# Smart_Light_Panel4.net
KiCad netlist of a schematic drawn in EAGLE
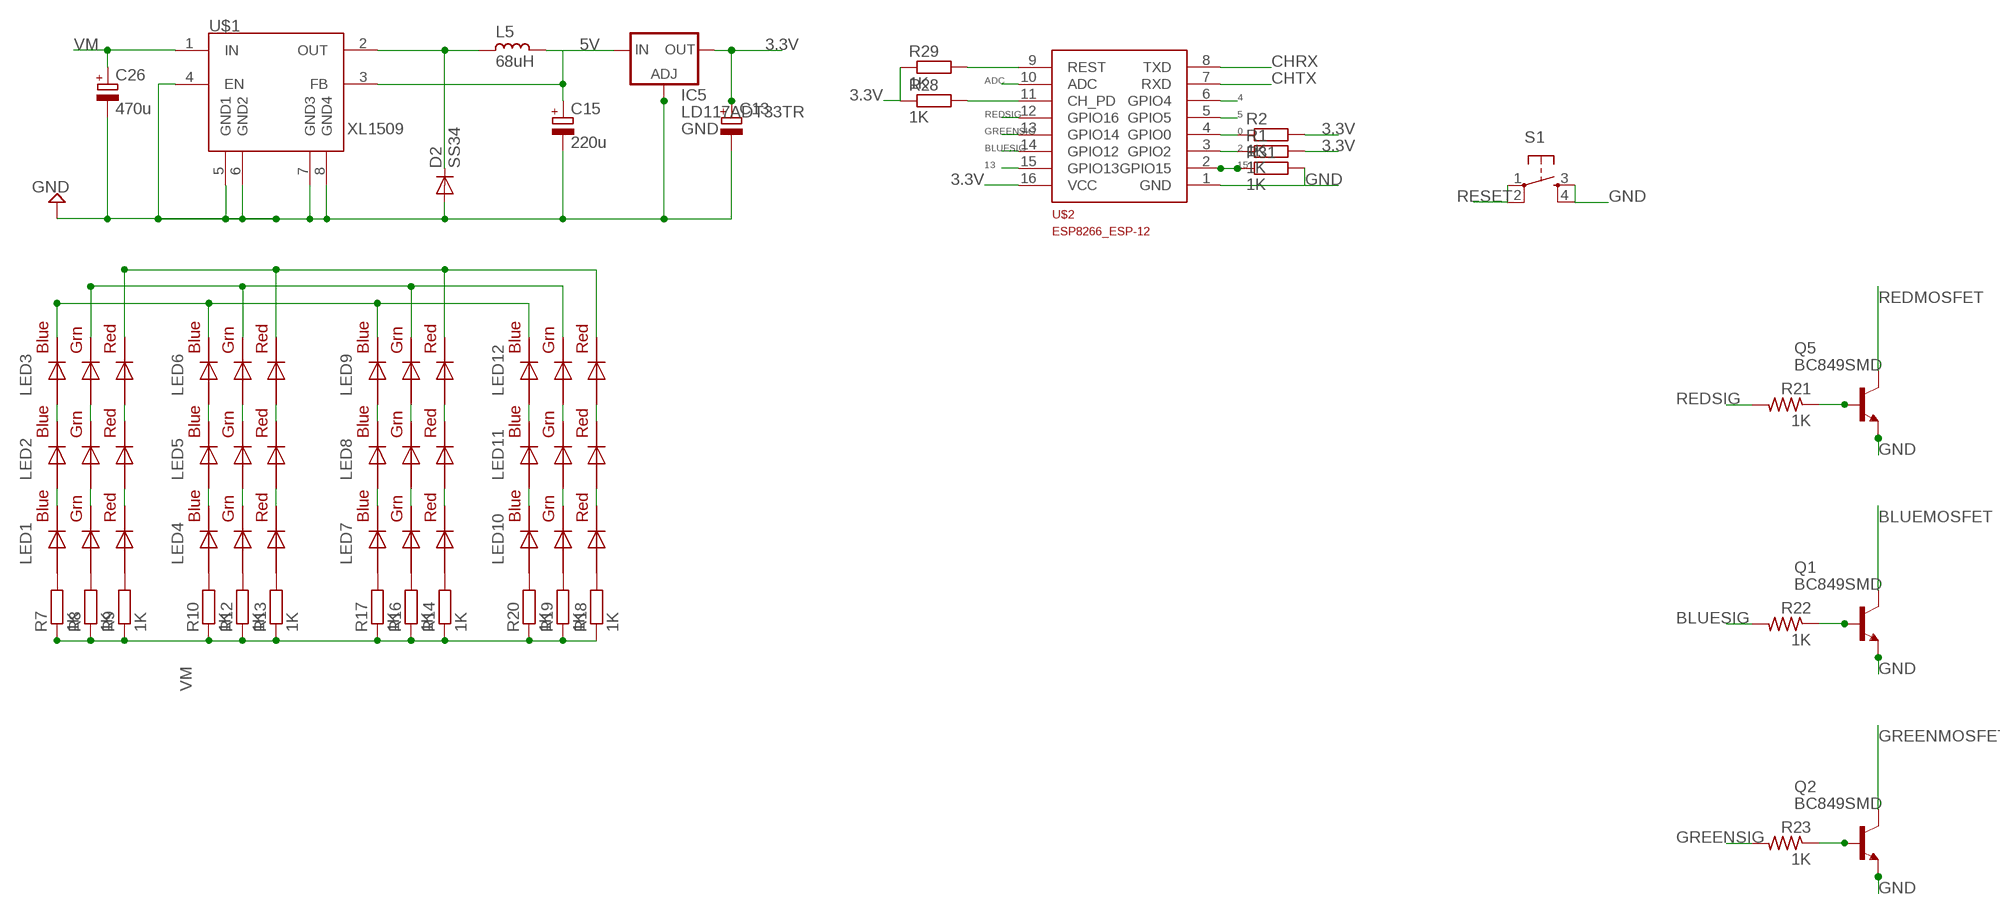
[diagram p0: schematic, sheet 1]

(export (version "E")
  (design (tool "Eeschema 10.0.6"))
  (components
    (comp (ref "C13")
      (value "CPOL-EUE2.5-7")
      (footprint "eagle-import:E2,5-7")
      (libsource (lib "eagle-import") (part "CPOL-EUE2.5-7"))
    )
    (comp (ref "C15")
      (value "220u")
      (footprint "eagle-import:E2,5-7")
      (libsource (lib "eagle-import") (part "CPOL-EUE2.5-7"))
    )
    (comp (ref "C26")
      (value "470u")
      (footprint "eagle-import:E2,5-7")
      (libsource (lib "eagle-import") (part "CPOL-EUE2.5-7"))
    )
    (comp (ref "D2")
      (value "SS34")
      (footprint "eagle-import:DO-214AC")
      (libsource (lib "eagle-import") (part "DIODE-DO-214AC"))
    )
    (comp (ref "IC5")
      (value "LD117ADT33TR")
      (footprint "eagle-import:DPACK")
      (libsource (lib "eagle-import") (part "LD117A?DT33TR"))
    )
    (comp (ref "L5")
      (value "68uH")
      (footprint "eagle-import:CD75")
      (libsource (lib "eagle-import") (part "L_CD75"))
    )
    (comp (ref "LED1")
      (value "RGBLED5050")
      (footprint "eagle-import:RGBLED5050")
      (libsource (lib "eagle-import") (part "RGBLED5050"))
    )
    (comp (ref "LED2")
      (value "RGBLED5050")
      (footprint "eagle-import:RGBLED5050")
      (libsource (lib "eagle-import") (part "RGBLED5050"))
    )
    (comp (ref "LED3")
      (value "RGBLED5050")
      (footprint "eagle-import:RGBLED5050")
      (libsource (lib "eagle-import") (part "RGBLED5050"))
    )
    (comp (ref "LED4")
      (value "RGBLED5050")
      (footprint "eagle-import:RGBLED5050")
      (libsource (lib "eagle-import") (part "RGBLED5050"))
    )
    (comp (ref "LED5")
      (value "RGBLED5050")
      (footprint "eagle-import:RGBLED5050")
      (libsource (lib "eagle-import") (part "RGBLED5050"))
    )
    (comp (ref "LED6")
      (value "RGBLED5050")
      (footprint "eagle-import:RGBLED5050")
      (libsource (lib "eagle-import") (part "RGBLED5050"))
    )
    (comp (ref "LED7")
      (value "RGBLED5050")
      (footprint "eagle-import:RGBLED5050")
      (libsource (lib "eagle-import") (part "RGBLED5050"))
    )
    (comp (ref "LED8")
      (value "RGBLED5050")
      (footprint "eagle-import:RGBLED5050")
      (libsource (lib "eagle-import") (part "RGBLED5050"))
    )
    (comp (ref "LED9")
      (value "RGBLED5050")
      (footprint "eagle-import:RGBLED5050")
      (libsource (lib "eagle-import") (part "RGBLED5050"))
    )
    (comp (ref "LED10")
      (value "RGBLED5050")
      (footprint "eagle-import:RGBLED5050")
      (libsource (lib "eagle-import") (part "RGBLED5050"))
    )
    (comp (ref "LED11")
      (value "RGBLED5050")
      (footprint "eagle-import:RGBLED5050")
      (libsource (lib "eagle-import") (part "RGBLED5050"))
    )
    (comp (ref "LED12")
      (value "RGBLED5050")
      (footprint "eagle-import:RGBLED5050")
      (libsource (lib "eagle-import") (part "RGBLED5050"))
    )
    (comp (ref "Q1")
      (value "BC849SMD")
      (footprint "eagle-import:SOT23-BEC")
      (libsource (lib "eagle-import") (part "BC849SMD"))
    )
    (comp (ref "Q2")
      (value "BC849SMD")
      (footprint "eagle-import:SOT23-BEC")
      (libsource (lib "eagle-import") (part "BC849SMD"))
    )
    (comp (ref "Q5")
      (value "BC849SMD")
      (footprint "eagle-import:SOT23-BEC")
      (libsource (lib "eagle-import") (part "BC849SMD"))
    )
    (comp (ref "R1")
      (value "1K")
      (footprint "eagle-import:M1206")
      (libsource (lib "eagle-import") (part "R-EU_M1206"))
    )
    (comp (ref "R2")
      (value "1K")
      (footprint "eagle-import:M1206")
      (libsource (lib "eagle-import") (part "R-EU_M1206"))
    )
    (comp (ref "R7")
      (value "1K")
      (footprint "eagle-import:R1206")
      (libsource (lib "eagle-import") (part "R-EU_R1206"))
    )
    (comp (ref "R8")
      (value "1K")
      (footprint "eagle-import:R1206")
      (libsource (lib "eagle-import") (part "R-EU_R1206"))
    )
    (comp (ref "R9")
      (value "1K")
      (footprint "eagle-import:R1206")
      (libsource (lib "eagle-import") (part "R-EU_R1206"))
    )
    (comp (ref "R10")
      (value "1K")
      (footprint "eagle-import:R1206")
      (libsource (lib "eagle-import") (part "R-EU_R1206"))
    )
    (comp (ref "R12")
      (value "1K")
      (footprint "eagle-import:R1206")
      (libsource (lib "eagle-import") (part "R-EU_R1206"))
    )
    (comp (ref "R13")
      (value "1K")
      (footprint "eagle-import:R1206")
      (libsource (lib "eagle-import") (part "R-EU_R1206"))
    )
    (comp (ref "R14")
      (value "1K")
      (footprint "eagle-import:R1206")
      (libsource (lib "eagle-import") (part "R-EU_R1206"))
    )
    (comp (ref "R16")
      (value "1K")
      (footprint "eagle-import:R1206")
      (libsource (lib "eagle-import") (part "R-EU_R1206"))
    )
    (comp (ref "R17")
      (value "1K")
      (footprint "eagle-import:R1206")
      (libsource (lib "eagle-import") (part "R-EU_R1206"))
    )
    (comp (ref "R18")
      (value "1K")
      (footprint "eagle-import:R1206")
      (libsource (lib "eagle-import") (part "R-EU_R1206"))
    )
    (comp (ref "R19")
      (value "1K")
      (footprint "eagle-import:R1206")
      (libsource (lib "eagle-import") (part "R-EU_R1206"))
    )
    (comp (ref "R20")
      (value "1K")
      (footprint "eagle-import:R1206")
      (libsource (lib "eagle-import") (part "R-EU_R1206"))
    )
    (comp (ref "R21")
      (value "1K")
      (footprint "eagle-import:M1206")
      (libsource (lib "eagle-import") (part "R-US_M1206"))
    )
    (comp (ref "R22")
      (value "1K")
      (footprint "eagle-import:M1206")
      (libsource (lib "eagle-import") (part "R-US_M1206"))
    )
    (comp (ref "R23")
      (value "1K")
      (footprint "eagle-import:M1206")
      (libsource (lib "eagle-import") (part "R-US_M1206"))
    )
    (comp (ref "R28")
      (value "1K")
      (footprint "eagle-import:M1206")
      (libsource (lib "eagle-import") (part "R-EU_M1206"))
    )
    (comp (ref "R29")
      (value "1K")
      (footprint "eagle-import:M1206")
      (libsource (lib "eagle-import") (part "R-EU_M1206"))
    )
    (comp (ref "R31")
      (value "1K")
      (footprint "eagle-import:M1206")
      (libsource (lib "eagle-import") (part "R-EU_M1206"))
    )
    (comp (ref "S1")
      (value "TAC_SWITCHPTH")
      (footprint "eagle-import:TACTILE-PTH")
      (libsource (lib "eagle-import") (part "TAC_SWITCHPTH"))
    )
    (comp (ref "U$1")
      (value "XL1509")
      (footprint "eagle-import:SO08")
      (libsource (lib "eagle-import") (part "XL1509"))
    )
    (comp (ref "U$2")
      (value "ESP8266_ESP-12")
      (footprint "eagle-import:ESP8266-ESP12")
      (libsource (lib "eagle-import") (part "ESP8266_ESP-12"))
    )
  )
  (nets
    (net (code "1") (name "/0") (class "Default")
      (node (ref "R2") (pin "1") (pinfunction "1_1") (pintype "passive"))
      (node (ref "U$2") (pin "4") (pinfunction "GPIO0_4") (pintype "bidirectional"))
    )
    (net (code "2") (name "/2") (class "Default")
      (node (ref "R1") (pin "1") (pinfunction "1_1") (pintype "passive"))
      (node (ref "U$2") (pin "3") (pinfunction "GPIO2_3") (pintype "bidirectional"))
    )
    (net (code "3") (name "/3.3V") (class "Default")
      (node (ref "C13") (pin "+") (pinfunction "+_+") (pintype "passive"))
      (node (ref "IC5") (pin "4") (pinfunction "OUT_4") (pintype "passive"))
      (node (ref "R1") (pin "2") (pinfunction "2_2") (pintype "passive"))
      (node (ref "R2") (pin "2") (pinfunction "2_2") (pintype "passive"))
      (node (ref "R28") (pin "1") (pinfunction "1_1") (pintype "passive"))
      (node (ref "R29") (pin "1") (pinfunction "1_1") (pintype "passive"))
      (node (ref "U$2") (pin "16") (pinfunction "VCC_16") (pintype "bidirectional"))
    )
    (net (code "4") (name "/4") (class "Default")
      (node (ref "U$2") (pin "6") (pinfunction "GPIO4_6") (pintype "bidirectional"))
    )
    (net (code "5") (name "/5") (class "Default")
      (node (ref "U$2") (pin "5") (pinfunction "GPIO5_5") (pintype "bidirectional"))
    )
    (net (code "6") (name "/5V") (class "Default")
      (node (ref "C15") (pin "+") (pinfunction "+_+") (pintype "passive"))
      (node (ref "IC5") (pin "3") (pinfunction "IN_3") (pintype "input"))
      (node (ref "L5") (pin "1") (pinfunction "1_1") (pintype "passive"))
      (node (ref "U$1") (pin "3") (pinfunction "FB_3") (pintype "bidirectional"))
    )
    (net (code "7") (name "/13") (class "Default")
      (node (ref "U$2") (pin "15") (pinfunction "GPIO13_15") (pintype "bidirectional"))
    )
    (net (code "8") (name "/15") (class "Default")
      (node (ref "R31") (pin "1") (pinfunction "1_1") (pintype "passive"))
      (node (ref "U$2") (pin "2") (pinfunction "GPIO15_2") (pintype "bidirectional"))
    )
    (net (code "9") (name "/ADC") (class "Default")
      (node (ref "U$2") (pin "10") (pinfunction "ADC_10") (pintype "bidirectional"))
    )
    (net (code "10") (name "/BLUEMOSFET") (class "Default")
      (node (ref "LED12") (pin "4") (pinfunction "BLUE_C_4") (pintype "bidirectional"))
      (node (ref "LED3") (pin "4") (pinfunction "BLUE_C_4") (pintype "bidirectional"))
      (node (ref "LED6") (pin "4") (pinfunction "BLUE_C_4") (pintype "bidirectional"))
      (node (ref "LED9") (pin "4") (pinfunction "BLUE_C_4") (pintype "bidirectional"))
      (node (ref "Q1") (pin "C") (pinfunction "C_C") (pintype "passive"))
    )
    (net (code "11") (name "/BLUESIG") (class "Default")
      (node (ref "R22") (pin "2") (pinfunction "2_2") (pintype "passive"))
      (node (ref "U$2") (pin "14") (pinfunction "GPIO12_14") (pintype "bidirectional"))
    )
    (net (code "12") (name "/CHRX") (class "Default")
      (node (ref "U$2") (pin "8") (pinfunction "TXD_8") (pintype "bidirectional"))
    )
    (net (code "13") (name "/CHTX") (class "Default")
      (node (ref "U$2") (pin "7") (pinfunction "RXD_7") (pintype "bidirectional"))
    )
    (net (code "14") (name "/GREENMOSFET") (class "Default")
      (node (ref "LED12") (pin "6") (pinfunction "GREEN_C_6") (pintype "bidirectional"))
      (node (ref "LED3") (pin "6") (pinfunction "GREEN_C_6") (pintype "bidirectional"))
      (node (ref "LED6") (pin "6") (pinfunction "GREEN_C_6") (pintype "bidirectional"))
      (node (ref "LED9") (pin "6") (pinfunction "GREEN_C_6") (pintype "bidirectional"))
      (node (ref "Q2") (pin "C") (pinfunction "C_C") (pintype "passive"))
    )
    (net (code "15") (name "/GREENSIG") (class "Default")
      (node (ref "R23") (pin "2") (pinfunction "2_2") (pintype "passive"))
      (node (ref "U$2") (pin "13") (pinfunction "GPIO14_13") (pintype "bidirectional"))
    )
    (net (code "16") (name "/REDMOSFET") (class "Default")
      (node (ref "LED12") (pin "5") (pinfunction "RED_C_5") (pintype "bidirectional"))
      (node (ref "LED3") (pin "5") (pinfunction "RED_C_5") (pintype "bidirectional"))
      (node (ref "LED6") (pin "5") (pinfunction "RED_C_5") (pintype "bidirectional"))
      (node (ref "LED9") (pin "5") (pinfunction "RED_C_5") (pintype "bidirectional"))
      (node (ref "Q5") (pin "C") (pinfunction "C_C") (pintype "passive"))
    )
    (net (code "17") (name "/REDSIG") (class "Default")
      (node (ref "R21") (pin "2") (pinfunction "2_2") (pintype "passive"))
      (node (ref "U$2") (pin "12") (pinfunction "GPIO16_12") (pintype "bidirectional"))
    )
    (net (code "18") (name "/RESET") (class "Default")
      (node (ref "R29") (pin "2") (pinfunction "2_2") (pintype "passive"))
      (node (ref "S1") (pin "1") (pinfunction "1_1") (pintype "passive"))
      (node (ref "S1") (pin "2") (pinfunction "2_2") (pintype "passive"))
      (node (ref "U$2") (pin "9") (pinfunction "REST_9") (pintype "bidirectional"))
    )
    (net (code "19") (name "/VM") (class "Default")
      (node (ref "C26") (pin "+") (pinfunction "+_+") (pintype "passive"))
      (node (ref "R10") (pin "1") (pinfunction "1_1") (pintype "passive"))
      (node (ref "R12") (pin "1") (pinfunction "1_1") (pintype "passive"))
      (node (ref "R13") (pin "1") (pinfunction "1_1") (pintype "passive"))
      (node (ref "R14") (pin "1") (pinfunction "1_1") (pintype "passive"))
      (node (ref "R16") (pin "1") (pinfunction "1_1") (pintype "passive"))
      (node (ref "R17") (pin "1") (pinfunction "1_1") (pintype "passive"))
      (node (ref "R18") (pin "1") (pinfunction "1_1") (pintype "passive"))
      (node (ref "R19") (pin "1") (pinfunction "1_1") (pintype "passive"))
      (node (ref "R20") (pin "1") (pinfunction "1_1") (pintype "passive"))
      (node (ref "R7") (pin "1") (pinfunction "1_1") (pintype "passive"))
      (node (ref "R8") (pin "1") (pinfunction "1_1") (pintype "passive"))
      (node (ref "R9") (pin "1") (pinfunction "1_1") (pintype "passive"))
      (node (ref "U$1") (pin "1") (pinfunction "IN_1") (pintype "bidirectional"))
    )
    (net (code "20") (name "GND") (class "Default")
      (node (ref "C13") (pin "-") (pinfunction "-_-") (pintype "passive"))
      (node (ref "C15") (pin "-") (pinfunction "-_-") (pintype "passive"))
      (node (ref "C26") (pin "-") (pinfunction "-_-") (pintype "passive"))
      (node (ref "D2") (pin "2") (pinfunction "A_2") (pintype "passive"))
      (node (ref "IC5") (pin "1") (pinfunction "ADJ_1") (pintype "input"))
      (node (ref "Q1") (pin "E") (pinfunction "E_E") (pintype "passive"))
      (node (ref "Q2") (pin "E") (pinfunction "E_E") (pintype "passive"))
      (node (ref "Q5") (pin "E") (pinfunction "E_E") (pintype "passive"))
      (node (ref "R31") (pin "2") (pinfunction "2_2") (pintype "passive"))
      (node (ref "S1") (pin "3") (pinfunction "3_3") (pintype "passive"))
      (node (ref "S1") (pin "4") (pinfunction "4_4") (pintype "passive"))
      (node (ref "U$1") (pin "4") (pinfunction "EN_4") (pintype "bidirectional"))
      (node (ref "U$1") (pin "5") (pinfunction "GND1_5") (pintype "bidirectional"))
      (node (ref "U$1") (pin "6") (pinfunction "GND2_6") (pintype "bidirectional"))
      (node (ref "U$1") (pin "7") (pinfunction "GND3_7") (pintype "bidirectional"))
      (node (ref "U$1") (pin "8") (pinfunction "GND4_8") (pintype "bidirectional"))
      (node (ref "U$2") (pin "1") (pinfunction "GND_1") (pintype "bidirectional"))
    )
    (net (code "21") (name "Net-(D2-C)") (class "Default")
      (node (ref "D2") (pin "1") (pinfunction "C_1") (pintype "passive"))
      (node (ref "L5") (pin "2") (pinfunction "2_2") (pintype "passive"))
      (node (ref "U$1") (pin "2") (pinfunction "OUT_2") (pintype "bidirectional"))
    )
    (net (code "22") (name "Net-(LED1-BLUE_A)") (class "Default")
      (node (ref "LED1") (pin "3") (pinfunction "BLUE_A_3") (pintype "bidirectional"))
      (node (ref "R7") (pin "2") (pinfunction "2_2") (pintype "passive"))
    )
    (net (code "23") (name "Net-(LED1-BLUE_C)") (class "Default")
      (node (ref "LED1") (pin "4") (pinfunction "BLUE_C_4") (pintype "bidirectional"))
      (node (ref "LED2") (pin "3") (pinfunction "BLUE_A_3") (pintype "bidirectional"))
    )
    (net (code "24") (name "Net-(LED1-GREEN_A)") (class "Default")
      (node (ref "LED1") (pin "1") (pinfunction "GREEN_A_1") (pintype "bidirectional"))
      (node (ref "R8") (pin "2") (pinfunction "2_2") (pintype "passive"))
    )
    (net (code "25") (name "Net-(LED1-GREEN_C)") (class "Default")
      (node (ref "LED1") (pin "6") (pinfunction "GREEN_C_6") (pintype "bidirectional"))
      (node (ref "LED2") (pin "1") (pinfunction "GREEN_A_1") (pintype "bidirectional"))
    )
    (net (code "26") (name "Net-(LED1-RED_A)") (class "Default")
      (node (ref "LED1") (pin "2") (pinfunction "RED_A_2") (pintype "bidirectional"))
      (node (ref "R9") (pin "2") (pinfunction "2_2") (pintype "passive"))
    )
    (net (code "27") (name "Net-(LED1-RED_C)") (class "Default")
      (node (ref "LED1") (pin "5") (pinfunction "RED_C_5") (pintype "bidirectional"))
      (node (ref "LED2") (pin "2") (pinfunction "RED_A_2") (pintype "bidirectional"))
    )
    (net (code "28") (name "Net-(LED2-BLUE_C)") (class "Default")
      (node (ref "LED2") (pin "4") (pinfunction "BLUE_C_4") (pintype "bidirectional"))
      (node (ref "LED3") (pin "3") (pinfunction "BLUE_A_3") (pintype "bidirectional"))
    )
    (net (code "29") (name "Net-(LED2-GREEN_C)") (class "Default")
      (node (ref "LED2") (pin "6") (pinfunction "GREEN_C_6") (pintype "bidirectional"))
      (node (ref "LED3") (pin "1") (pinfunction "GREEN_A_1") (pintype "bidirectional"))
    )
    (net (code "30") (name "Net-(LED2-RED_C)") (class "Default")
      (node (ref "LED2") (pin "5") (pinfunction "RED_C_5") (pintype "bidirectional"))
      (node (ref "LED3") (pin "2") (pinfunction "RED_A_2") (pintype "bidirectional"))
    )
    (net (code "31") (name "Net-(LED4-BLUE_A)") (class "Default")
      (node (ref "LED4") (pin "3") (pinfunction "BLUE_A_3") (pintype "bidirectional"))
      (node (ref "R10") (pin "2") (pinfunction "2_2") (pintype "passive"))
    )
    (net (code "32") (name "Net-(LED4-BLUE_C)") (class "Default")
      (node (ref "LED4") (pin "4") (pinfunction "BLUE_C_4") (pintype "bidirectional"))
      (node (ref "LED5") (pin "3") (pinfunction "BLUE_A_3") (pintype "bidirectional"))
    )
    (net (code "33") (name "Net-(LED4-GREEN_A)") (class "Default")
      (node (ref "LED4") (pin "1") (pinfunction "GREEN_A_1") (pintype "bidirectional"))
      (node (ref "R12") (pin "2") (pinfunction "2_2") (pintype "passive"))
    )
    (net (code "34") (name "Net-(LED4-GREEN_C)") (class "Default")
      (node (ref "LED4") (pin "6") (pinfunction "GREEN_C_6") (pintype "bidirectional"))
      (node (ref "LED5") (pin "1") (pinfunction "GREEN_A_1") (pintype "bidirectional"))
    )
    (net (code "35") (name "Net-(LED4-RED_A)") (class "Default")
      (node (ref "LED4") (pin "2") (pinfunction "RED_A_2") (pintype "bidirectional"))
      (node (ref "R13") (pin "2") (pinfunction "2_2") (pintype "passive"))
    )
    (net (code "36") (name "Net-(LED4-RED_C)") (class "Default")
      (node (ref "LED4") (pin "5") (pinfunction "RED_C_5") (pintype "bidirectional"))
      (node (ref "LED5") (pin "2") (pinfunction "RED_A_2") (pintype "bidirectional"))
    )
    (net (code "37") (name "Net-(LED5-BLUE_C)") (class "Default")
      (node (ref "LED5") (pin "4") (pinfunction "BLUE_C_4") (pintype "bidirectional"))
      (node (ref "LED6") (pin "3") (pinfunction "BLUE_A_3") (pintype "bidirectional"))
    )
    (net (code "38") (name "Net-(LED5-GREEN_C)") (class "Default")
      (node (ref "LED5") (pin "6") (pinfunction "GREEN_C_6") (pintype "bidirectional"))
      (node (ref "LED6") (pin "1") (pinfunction "GREEN_A_1") (pintype "bidirectional"))
    )
    (net (code "39") (name "Net-(LED5-RED_C)") (class "Default")
      (node (ref "LED5") (pin "5") (pinfunction "RED_C_5") (pintype "bidirectional"))
      (node (ref "LED6") (pin "2") (pinfunction "RED_A_2") (pintype "bidirectional"))
    )
    (net (code "40") (name "Net-(LED7-BLUE_A)") (class "Default")
      (node (ref "LED7") (pin "3") (pinfunction "BLUE_A_3") (pintype "bidirectional"))
      (node (ref "R17") (pin "2") (pinfunction "2_2") (pintype "passive"))
    )
    (net (code "41") (name "Net-(LED7-BLUE_C)") (class "Default")
      (node (ref "LED7") (pin "4") (pinfunction "BLUE_C_4") (pintype "bidirectional"))
      (node (ref "LED8") (pin "3") (pinfunction "BLUE_A_3") (pintype "bidirectional"))
    )
    (net (code "42") (name "Net-(LED7-GREEN_A)") (class "Default")
      (node (ref "LED7") (pin "1") (pinfunction "GREEN_A_1") (pintype "bidirectional"))
      (node (ref "R16") (pin "2") (pinfunction "2_2") (pintype "passive"))
    )
    (net (code "43") (name "Net-(LED7-GREEN_C)") (class "Default")
      (node (ref "LED7") (pin "6") (pinfunction "GREEN_C_6") (pintype "bidirectional"))
      (node (ref "LED8") (pin "1") (pinfunction "GREEN_A_1") (pintype "bidirectional"))
    )
    (net (code "44") (name "Net-(LED7-RED_A)") (class "Default")
      (node (ref "LED7") (pin "2") (pinfunction "RED_A_2") (pintype "bidirectional"))
      (node (ref "R14") (pin "2") (pinfunction "2_2") (pintype "passive"))
    )
    (net (code "45") (name "Net-(LED7-RED_C)") (class "Default")
      (node (ref "LED7") (pin "5") (pinfunction "RED_C_5") (pintype "bidirectional"))
      (node (ref "LED8") (pin "2") (pinfunction "RED_A_2") (pintype "bidirectional"))
    )
    (net (code "46") (name "Net-(LED8-BLUE_C)") (class "Default")
      (node (ref "LED8") (pin "4") (pinfunction "BLUE_C_4") (pintype "bidirectional"))
      (node (ref "LED9") (pin "3") (pinfunction "BLUE_A_3") (pintype "bidirectional"))
    )
    (net (code "47") (name "Net-(LED8-GREEN_C)") (class "Default")
      (node (ref "LED8") (pin "6") (pinfunction "GREEN_C_6") (pintype "bidirectional"))
      (node (ref "LED9") (pin "1") (pinfunction "GREEN_A_1") (pintype "bidirectional"))
    )
    (net (code "48") (name "Net-(LED8-RED_C)") (class "Default")
      (node (ref "LED8") (pin "5") (pinfunction "RED_C_5") (pintype "bidirectional"))
      (node (ref "LED9") (pin "2") (pinfunction "RED_A_2") (pintype "bidirectional"))
    )
    (net (code "49") (name "Net-(LED10-BLUE_A)") (class "Default")
      (node (ref "LED10") (pin "3") (pinfunction "BLUE_A_3") (pintype "bidirectional"))
      (node (ref "R20") (pin "2") (pinfunction "2_2") (pintype "passive"))
    )
    (net (code "50") (name "Net-(LED10-BLUE_C)") (class "Default")
      (node (ref "LED10") (pin "4") (pinfunction "BLUE_C_4") (pintype "bidirectional"))
      (node (ref "LED11") (pin "3") (pinfunction "BLUE_A_3") (pintype "bidirectional"))
    )
    (net (code "51") (name "Net-(LED10-GREEN_A)") (class "Default")
      (node (ref "LED10") (pin "1") (pinfunction "GREEN_A_1") (pintype "bidirectional"))
      (node (ref "R19") (pin "2") (pinfunction "2_2") (pintype "passive"))
    )
    (net (code "52") (name "Net-(LED10-GREEN_C)") (class "Default")
      (node (ref "LED10") (pin "6") (pinfunction "GREEN_C_6") (pintype "bidirectional"))
      (node (ref "LED11") (pin "1") (pinfunction "GREEN_A_1") (pintype "bidirectional"))
    )
    (net (code "53") (name "Net-(LED10-RED_A)") (class "Default")
      (node (ref "LED10") (pin "2") (pinfunction "RED_A_2") (pintype "bidirectional"))
      (node (ref "R18") (pin "2") (pinfunction "2_2") (pintype "passive"))
    )
    (net (code "54") (name "Net-(LED10-RED_C)") (class "Default")
      (node (ref "LED10") (pin "5") (pinfunction "RED_C_5") (pintype "bidirectional"))
      (node (ref "LED11") (pin "2") (pinfunction "RED_A_2") (pintype "bidirectional"))
    )
    (net (code "55") (name "Net-(LED11-BLUE_C)") (class "Default")
      (node (ref "LED11") (pin "4") (pinfunction "BLUE_C_4") (pintype "bidirectional"))
      (node (ref "LED12") (pin "3") (pinfunction "BLUE_A_3") (pintype "bidirectional"))
    )
    (net (code "56") (name "Net-(LED11-GREEN_C)") (class "Default")
      (node (ref "LED11") (pin "6") (pinfunction "GREEN_C_6") (pintype "bidirectional"))
      (node (ref "LED12") (pin "1") (pinfunction "GREEN_A_1") (pintype "bidirectional"))
    )
    (net (code "57") (name "Net-(LED11-RED_C)") (class "Default")
      (node (ref "LED11") (pin "5") (pinfunction "RED_C_5") (pintype "bidirectional"))
      (node (ref "LED12") (pin "2") (pinfunction "RED_A_2") (pintype "bidirectional"))
    )
    (net (code "58") (name "Net-(Q1-PadB)") (class "Default")
      (node (ref "Q1") (pin "B") (pinfunction "B_B") (pintype "passive"))
      (node (ref "R22") (pin "1") (pinfunction "1_1") (pintype "passive"))
    )
    (net (code "59") (name "Net-(Q2-PadB)") (class "Default")
      (node (ref "Q2") (pin "B") (pinfunction "B_B") (pintype "passive"))
      (node (ref "R23") (pin "1") (pinfunction "1_1") (pintype "passive"))
    )
    (net (code "60") (name "Net-(Q5-PadB)") (class "Default")
      (node (ref "Q5") (pin "B") (pinfunction "B_B") (pintype "passive"))
      (node (ref "R21") (pin "1") (pinfunction "1_1") (pintype "passive"))
    )
    (net (code "61") (name "Net-(U$2-CH_PD)") (class "Default")
      (node (ref "R28") (pin "2") (pinfunction "2_2") (pintype "passive"))
      (node (ref "U$2") (pin "11") (pinfunction "CH_PD_11") (pintype "bidirectional"))
    )
  )
)
